# TSAL_PL.net
KiCad netlist of a schematic drawn in Altium Designer
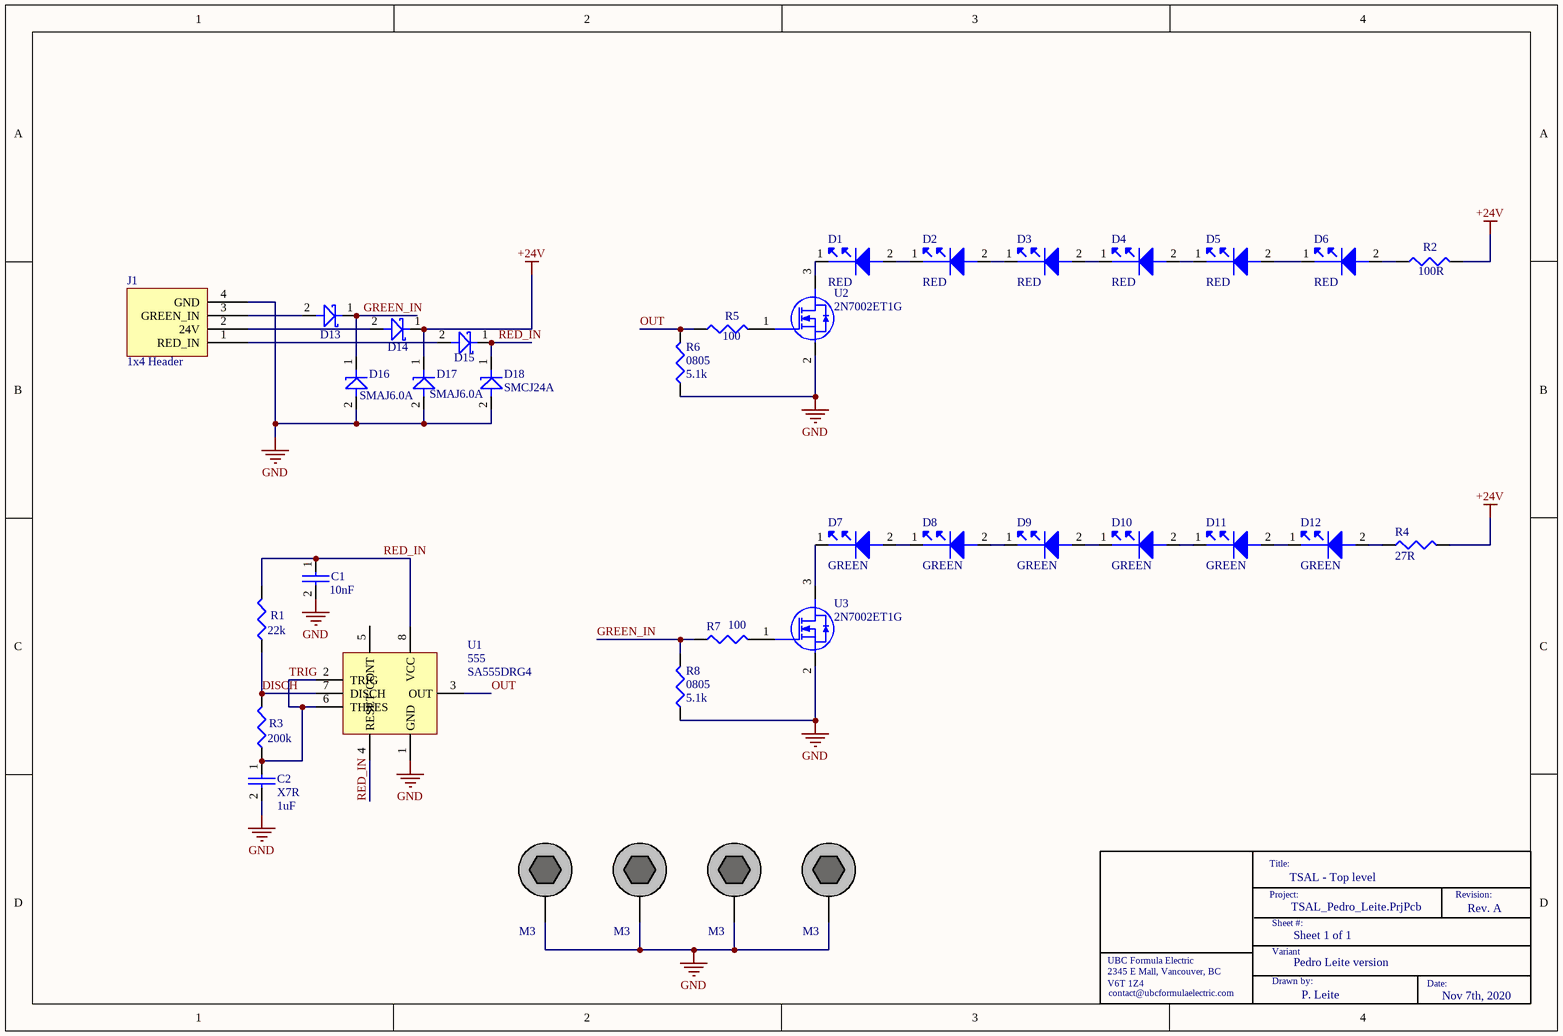
[diagram p0: TSAL_PL.SchDoc]

(export (version "E")
  (design (tool "Eeschema 10.0.6"))
  (components
    (comp (ref "*") (value "Title Box") (libsource (lib "TSAL_PL") (part "Title Box")))
    (comp (ref "2")
      (value "M3")
      (footprint "M3 Mounting Hole")
      (libsource (lib "UBC Formula Electric") (part "M3 Mounting Hole"))
    )
    (comp (ref "3")
      (value "M3")
      (footprint "M3 Mounting Hole")
      (libsource (lib "UBC Formula Electric") (part "M3 Mounting Hole"))
    )
    (comp (ref "4")
      (value "M3")
      (footprint "M3 Mounting Hole")
      (libsource (lib "UBC Formula Electric") (part "M3 Mounting Hole"))
    )
    (comp (ref "C1")
      (value "0603")
      (footprint "0603 CAPACITOR (TDK C-SERIES)")
      (description "Cap Ceramic 0.01uF 50VDC X7R 10% SMD 0603 Paper T/R")
      (fields
        (field (name "MANUFACTURER") "Samsung")
        (field (name "MANUFACTURER PART NUMBER") "CL10B103KB8NNNC")
        (field (name "CAPACITANCE") "10nF")
      )
      (libsource (lib "TSAL_PL") (part "CL10B103KB8NNNC"))
    )
    (comp (ref "C2")
      (value "X7R")
      (footprint "RESC0805X60N")
      (fields
        (field (name "MANUFACTURER") "Yageo")
        (field (name "MANUFACTURER PART NUMBER") "CC0805KKX7R6BB105")
        (field (name "TOLERANCE") "10%")
        (field (name "CAPACITANCE") "1uF")
      )
      (libsource (lib "TSAL_PL") (part "CC0805KKX7R6BB105"))
    )
    (comp (ref "D1")
      (value "RED")
      (footprint "RED LED")
      (description "LED 0.33W RED WTR CLR 3.5MM")
      (fields (field (name "MANUFACTURER") "TT Optek") (field (name "MANUFACTURER PART NUMBER") "OVS5MRBCR4"))
      (libsource (lib "TSAL_PL") (part "OVS5MRBCR4"))
    )
    (comp (ref "D2")
      (value "RED")
      (footprint "RED LED")
      (description "LED 0.33W RED WTR CLR 3.5MM")
      (fields (field (name "MANUFACTURER") "TT Optek") (field (name "MANUFACTURER PART NUMBER") "OVS5MRBCR4"))
      (libsource (lib "TSAL_PL") (part "OVS5MRBCR4"))
    )
    (comp (ref "D3")
      (value "RED")
      (footprint "RED LED")
      (description "LED 0.33W RED WTR CLR 3.5MM")
      (fields (field (name "MANUFACTURER") "TT Optek") (field (name "MANUFACTURER PART NUMBER") "OVS5MRBCR4"))
      (libsource (lib "TSAL_PL") (part "OVS5MRBCR4"))
    )
    (comp (ref "D4")
      (value "RED")
      (footprint "RED LED")
      (description "LED 0.33W RED WTR CLR 3.5MM")
      (fields (field (name "MANUFACTURER") "TT Optek") (field (name "MANUFACTURER PART NUMBER") "OVS5MRBCR4"))
      (libsource (lib "TSAL_PL") (part "OVS5MRBCR4"))
    )
    (comp (ref "D5")
      (value "RED")
      (footprint "RED LED")
      (description "LED 0.33W RED WTR CLR 3.5MM")
      (fields (field (name "MANUFACTURER") "TT Optek") (field (name "MANUFACTURER PART NUMBER") "OVS5MRBCR4"))
      (libsource (lib "TSAL_PL") (part "OVS5MRBCR4"))
    )
    (comp (ref "D6")
      (value "RED")
      (footprint "RED LED")
      (description "LED 0.33W RED WTR CLR 3.5MM")
      (fields (field (name "MANUFACTURER") "TT Optek") (field (name "MANUFACTURER PART NUMBER") "OVS5MRBCR4"))
      (libsource (lib "TSAL_PL") (part "OVS5MRBCR4"))
    )
    (comp (ref "D7")
      (value "GREEN")
      (footprint "GREEN LED")
      (description "Led 3.5X2.8 0.5W SMD Green")
      (fields (field (name "MANUFACTURER") "SunLED") (field (name "MANUFACTURER PART NUMBER") "XZDG25X109FS"))
      (libsource (lib "TSAL_PL") (part "XZDG25X109FS"))
    )
    (comp (ref "D8")
      (value "GREEN")
      (footprint "GREEN LED")
      (description "Led 3.5X2.8 0.5W SMD Green")
      (fields (field (name "MANUFACTURER") "SunLED") (field (name "MANUFACTURER PART NUMBER") "XZDG25X109FS"))
      (libsource (lib "TSAL_PL") (part "XZDG25X109FS"))
    )
    (comp (ref "D9")
      (value "GREEN")
      (footprint "GREEN LED")
      (description "Led 3.5X2.8 0.5W SMD Green")
      (fields (field (name "MANUFACTURER") "SunLED") (field (name "MANUFACTURER PART NUMBER") "XZDG25X109FS"))
      (libsource (lib "TSAL_PL") (part "XZDG25X109FS"))
    )
    (comp (ref "D10")
      (value "GREEN")
      (footprint "GREEN LED")
      (description "Led 3.5X2.8 0.5W SMD Green")
      (fields (field (name "MANUFACTURER") "SunLED") (field (name "MANUFACTURER PART NUMBER") "XZDG25X109FS"))
      (libsource (lib "TSAL_PL") (part "XZDG25X109FS"))
    )
    (comp (ref "D11")
      (value "GREEN")
      (footprint "GREEN LED")
      (description "Led 3.5X2.8 0.5W SMD Green")
      (fields (field (name "MANUFACTURER") "SunLED") (field (name "MANUFACTURER PART NUMBER") "XZDG25X109FS"))
      (libsource (lib "TSAL_PL") (part "XZDG25X109FS"))
    )
    (comp (ref "D12")
      (value "GREEN")
      (footprint "GREEN LED")
      (description "Led 3.5X2.8 0.5W SMD Green")
      (fields (field (name "MANUFACTURER") "SunLED") (field (name "MANUFACTURER PART NUMBER") "XZDG25X109FS"))
      (libsource (lib "TSAL_PL") (part "XZDG25X109FS"))
    )
    (comp (ref "D13")
      (value "NRVTS260ESFT1G")
      (footprint "ON NRVTS260ESFT1G")
      (description "ON SEMICONDUCTOR - NRVTS260ESFT1G - Schottky Rectifier, 60 V, 2 A, Single, SOD-123, 2 Pins, 650 mV")
      (fields (field (name "MANUFACTURER") "ON Semiconductor"))
      (libsource (lib "TSAL_PL") (part "NRVTS260ESFT1G"))
    )
    (comp (ref "D14")
      (value "NRVTS260ESFT1G")
      (footprint "ON NRVTS260ESFT1G")
      (description "ON SEMICONDUCTOR - NRVTS260ESFT1G - Schottky Rectifier, 60 V, 2 A, Single, SOD-123, 2 Pins, 650 mV")
      (fields (field (name "MANUFACTURER") "ON Semiconductor"))
      (libsource (lib "TSAL_PL") (part "NRVTS260ESFT1G"))
    )
    (comp (ref "D15")
      (value "NRVTS260ESFT1G")
      (footprint "ON NRVTS260ESFT1G")
      (description "ON SEMICONDUCTOR - NRVTS260ESFT1G - Schottky Rectifier, 60 V, 2 A, Single, SOD-123, 2 Pins, 650 mV")
      (fields (field (name "MANUFACTURER") "ON Semiconductor"))
      (libsource (lib "TSAL_PL") (part "NRVTS260ESFT1G"))
    )
    (comp (ref "D16")
      (value "SMAJ6.0A")
      (footprint "LITTELFUSE SMAJ6.0A")
      (description "In a Pack of 25, Littelfuse SMAJ6.0A, Uni-Directional TVS Diode, 400W, 2-Pin DO-214AC")
      (fields (field (name "MANUFACTURER") "Littelfuse") (field (name "VOLTAGE") "60V"))
      (libsource (lib "TSAL_PL") (part "SMAJ6.0A"))
    )
    (comp (ref "D17")
      (value "SMAJ6.0A")
      (footprint "LITTELFUSE SMAJ6.0A")
      (description "In a Pack of 25, Littelfuse SMAJ6.0A, Uni-Directional TVS Diode, 400W, 2-Pin DO-214AC")
      (fields (field (name "MANUFACTURER") "Littelfuse") (field (name "VOLTAGE") "60V"))
      (libsource (lib "TSAL_PL") (part "SMAJ6.0A"))
    )
    (comp (ref "D18")
      (value "SMCJ24A")
      (footprint "LITTELFUSE SMCJ24A")
      (fields (field (name "MANUFACTURER") "Littelfuse"))
      (libsource (lib "TSAL_PL") (part "SMCJ24A"))
    )
    (comp (ref "J1")
      (value "1x4 Header")
      (footprint "HDR1x4")
      (description "Conn Wire to Board HDR 4 POS 2.54mm Solder ST Thru-Hole Bag")
      (fields (field (name "MANUFACTURER") "Molex") (field (name "MANUFACTURER PART NUMBER") "22-27-2041"))
      (libsource (lib "TSAL_PL") (part "22-27-2041"))
    )
    (comp (ref "M1")
      (value "M3")
      (footprint "M3 Mounting Hole")
      (libsource (lib "UBC Formula Electric") (part "M3 Mounting Hole"))
    )
    (comp (ref "R1")
      (value "0603")
      (footprint "0603 RESISTOR (YAGEO)")
      (description "Res Thick Film 0603 22K Ohm 1% 1/10W ±100ppm/°C Molded SMD Paper T/R")
      (fields
        (field (name "MANUFACTURER") "Vishay Semiconductors")
        (field (name "MANUFACTURER PART NUMBER") "CRCW060322K0FKEAC")
        (field (name "RESISTANCE") "22k")
      )
      (libsource (lib "TSAL_PL") (part "CRCW060322K0FKEAC"))
    )
    (comp (ref "R2")
      (value "2010")
      (footprint "2010 RESISTOR (YAGEO)")
      (description "TE CONNECTIVITY - CRGP2010F100R - RES, 100R, 1%, 1.25W, 2010, THICK FILM")
      (fields
        (field (name "MANUFACTURER") "TE Connectivity")
        (field (name "MANUFACTURER PART NUMBER") "CRGP2010F100R")
        (field (name "RESISTENCE") "100R")
      )
      (libsource (lib "TSAL_PL") (part "2010"))
    )
    (comp (ref "R3")
      (value "0603")
      (footprint "0603 RESISTOR (YAGEO)")
      (description "Res Thick Film 0603 200K Ohm 1% 1/10W ±100ppm/°C Molded SMD Paper T/R")
      (fields
        (field (name "MANUFACTURER") "Vishay")
        (field (name "MANUFACTURER PART NUMBER") "CRCW0603200KFKEAC")
        (field (name "RESISTANCE") "200k")
      )
      (libsource (lib "TSAL_PL") (part "CRCW0603200KFKEAC"))
    )
    (comp (ref "R4")
      (value "RL1220S-270-F")
      (footprint "0805 RESISTOR (YAGEO)")
      (description "RES SMD 27 OHM 1% 1/3W 0805")
      (fields (field (name "MANUFACTURER") "Susumu") (field (name "RESISTANCE") "27R"))
      (libsource (lib "TSAL_PL") (part "RL1220S-270-F"))
    )
    (comp (ref "R5")
      (value "0805")
      (footprint "0805 RESISTOR (YAGEO)")
      (description "RES SMD 100 OHM 0.5% 1/8W 0805")
      (fields
        (field (name "MANUFACTURER") "Yageo")
        (field (name "MANUFACTURER PART NUMBER") "RT0805DRD07100RL")
        (field (name "RESISTANCE") "100")
      )
      (libsource (lib "TSAL_PL") (part "RT0805DRD07100RL"))
    )
    (comp (ref "R6")
      (value "0805")
      (footprint "0805 RESISTOR (YAGEO)")
      (description "Res Thick Film 0805 5.1K Ohm 5% 0.125W(1/8W) ±100ppm/C Epoxy Pad SMD T/R")
      (fields
        (field (name "MANUFACTURER") "Yageo")
        (field (name "MANUFACTURER PART NUMBER") "RC0805JR-075K1L")
        (field (name "RESISTANCE") "5.1k")
      )
      (libsource (lib "TSAL_PL") (part "RC0805JR-075K1L"))
    )
    (comp (ref "R7")
      (value "0805")
      (footprint "0805 RESISTOR (YAGEO)")
      (description "RES SMD 100 OHM 0.5% 1/8W 0805")
      (fields
        (field (name "MANUFACTURER") "Yageo")
        (field (name "MANUFACTURER PART NUMBER") "RT0805DRD07100RL")
        (field (name "RESISTANCE") "100")
      )
      (libsource (lib "TSAL_PL") (part "RT0805DRD07100RL"))
    )
    (comp (ref "R8")
      (value "0805")
      (footprint "0805 RESISTOR (YAGEO)")
      (description "Res Thick Film 0805 5.1K Ohm 5% 0.125W(1/8W) ±100ppm/C Epoxy Pad SMD T/R")
      (fields
        (field (name "MANUFACTURER") "Yageo")
        (field (name "MANUFACTURER PART NUMBER") "RC0805JR-075K1L")
        (field (name "RESISTANCE") "5.1k")
      )
      (libsource (lib "TSAL_PL") (part "RC0805JR-075K1L"))
    )
    (comp (ref "U1")
      (value "555")
      (footprint "SOIC-8")
      (description "IC OSC SGL TIMER 100KHZ 8-SOIC")
      (fields
        (field (name "MANUFACTURER") "Texas Instruments")
        (field (name "MANUFACTURER PART NUMBER") "SA555DRG4")
      )
      (libsource (lib "TSAL_PL") (part "SA555DRG4"))
    )
    (comp (ref "U2")
      (value "2N7002ET1G")
      (footprint "2N7002ET1G")
      (description "Trans MOSFET N-CH 60V 0.26A 3-Pin SOT-23 T/R")
      (fields (field (name "MANUFACTURER") "ON Semiconductor"))
      (libsource (lib "TSAL_PL") (part "2N7002ET1G"))
    )
    (comp (ref "U3")
      (value "2N7002ET1G")
      (footprint "2N7002ET1G")
      (description "Trans MOSFET N-CH 60V 0.26A 3-Pin SOT-23 T/R")
      (fields (field (name "MANUFACTURER") "ON Semiconductor"))
      (libsource (lib "TSAL_PL") (part "2N7002ET1G"))
    )
  )
  (nets
    (net (code "1") (name "+24V") (class "Default")
      (node (ref "D14") (pin "1") (pinfunction "1_1") (pintype "passive"))
      (node (ref "D17") (pin "1") (pinfunction "1_1") (pintype "passive"))
      (node (ref "R2") (pin "2") (pinfunction "2_2") (pintype "passive"))
      (node (ref "R4") (pin "2") (pinfunction "2_2") (pintype "passive"))
    )
    (net (code "2") (name "/DISCH") (class "Default")
      (node (ref "R1") (pin "1") (pinfunction "1_1") (pintype "passive"))
      (node (ref "R3") (pin "2") (pinfunction "2_2") (pintype "passive"))
      (node (ref "U1") (pin "7") (pinfunction "DISCH_7") (pintype "passive"))
    )
    (net (code "3") (name "/GREEN_IN") (class "Default")
      (node (ref "D13") (pin "1") (pinfunction "1_1") (pintype "passive"))
      (node (ref "D16") (pin "1") (pinfunction "1_1") (pintype "passive"))
      (node (ref "R7") (pin "1") (pinfunction "1_1") (pintype "passive"))
      (node (ref "R8") (pin "2") (pinfunction "2_2") (pintype "passive"))
    )
    (net (code "4") (name "/OUT") (class "Default")
      (node (ref "R5") (pin "1") (pinfunction "1_1") (pintype "passive"))
      (node (ref "R6") (pin "2") (pinfunction "2_2") (pintype "passive"))
      (node (ref "U1") (pin "3") (pinfunction "OUT_3") (pintype "passive"))
    )
    (net (code "5") (name "/RED_IN") (class "Default")
      (node (ref "C1") (pin "1") (pinfunction "1_1") (pintype "passive"))
      (node (ref "D15") (pin "1") (pinfunction "1_1") (pintype "passive"))
      (node (ref "D18") (pin "1") (pinfunction "1_1") (pintype "passive"))
      (node (ref "R1") (pin "2") (pinfunction "2_2") (pintype "passive"))
      (node (ref "U1") (pin "4") (pinfunction "RESET_4") (pintype "passive"))
      (node (ref "U1") (pin "8") (pinfunction "VCC_8") (pintype "passive"))
    )
    (net (code "6") (name "/TRIG") (class "Default")
      (node (ref "C2") (pin "1") (pinfunction "1_1") (pintype "passive"))
      (node (ref "R3") (pin "1") (pinfunction "1_1") (pintype "passive"))
      (node (ref "U1") (pin "2") (pinfunction "TRIG_2") (pintype "passive"))
      (node (ref "U1") (pin "6") (pinfunction "THRES_6") (pintype "passive"))
    )
    (net (code "7") (name "GND") (class "Default")
      (node (ref "2") (pin "1") (pinfunction "1_1") (pintype "passive"))
      (node (ref "3") (pin "1") (pinfunction "1_1") (pintype "passive"))
      (node (ref "4") (pin "1") (pinfunction "1_1") (pintype "passive"))
      (node (ref "C1") (pin "2") (pinfunction "2_2") (pintype "passive"))
      (node (ref "C2") (pin "2") (pinfunction "2_2") (pintype "passive"))
      (node (ref "D16") (pin "2") (pinfunction "2_2") (pintype "passive"))
      (node (ref "D17") (pin "2") (pinfunction "2_2") (pintype "passive"))
      (node (ref "D18") (pin "2") (pinfunction "2_2") (pintype "passive"))
      (node (ref "J1") (pin "4") (pinfunction "GND_4") (pintype "passive"))
      (node (ref "M1") (pin "1") (pinfunction "1_1") (pintype "passive"))
      (node (ref "R6") (pin "1") (pinfunction "1_1") (pintype "passive"))
      (node (ref "R8") (pin "1") (pinfunction "1_1") (pintype "passive"))
      (node (ref "U1") (pin "1") (pinfunction "GND_1") (pintype "passive"))
      (node (ref "U2") (pin "2") (pinfunction "S_2") (pintype "passive"))
      (node (ref "U3") (pin "2") (pinfunction "S_2") (pintype "passive"))
    )
    (net (code "8") (name "Net-(D1-Pad2)") (class "Default")
      (node (ref "D1") (pin "2") (pinfunction "2_2") (pintype "passive"))
      (node (ref "D2") (pin "1") (pinfunction "1_1") (pintype "passive"))
    )
    (net (code "9") (name "Net-(D2-Pad2)") (class "Default")
      (node (ref "D2") (pin "2") (pinfunction "2_2") (pintype "passive"))
      (node (ref "D3") (pin "1") (pinfunction "1_1") (pintype "passive"))
    )
    (net (code "10") (name "Net-(D3-Pad2)") (class "Default")
      (node (ref "D3") (pin "2") (pinfunction "2_2") (pintype "passive"))
      (node (ref "D4") (pin "1") (pinfunction "1_1") (pintype "passive"))
    )
    (net (code "11") (name "Net-(D4-Pad2)") (class "Default")
      (node (ref "D4") (pin "2") (pinfunction "2_2") (pintype "passive"))
      (node (ref "D5") (pin "1") (pinfunction "1_1") (pintype "passive"))
    )
    (net (code "12") (name "Net-(D5-Pad2)") (class "Default")
      (node (ref "D5") (pin "2") (pinfunction "2_2") (pintype "passive"))
      (node (ref "D6") (pin "1") (pinfunction "1_1") (pintype "passive"))
    )
    (net (code "13") (name "Net-(D6-Pad2)") (class "Default")
      (node (ref "D6") (pin "2") (pinfunction "2_2") (pintype "passive"))
      (node (ref "R2") (pin "1") (pinfunction "1_1") (pintype "passive"))
    )
    (net (code "14") (name "Net-(D7-Pad2)") (class "Default")
      (node (ref "D7") (pin "2") (pinfunction "2_2") (pintype "passive"))
      (node (ref "D8") (pin "1") (pinfunction "1_1") (pintype "passive"))
    )
    (net (code "15") (name "Net-(D8-Pad2)") (class "Default")
      (node (ref "D8") (pin "2") (pinfunction "2_2") (pintype "passive"))
      (node (ref "D9") (pin "1") (pinfunction "1_1") (pintype "passive"))
    )
    (net (code "16") (name "Net-(D10-Pad1)") (class "Default")
      (node (ref "D10") (pin "1") (pinfunction "1_1") (pintype "passive"))
      (node (ref "D9") (pin "2") (pinfunction "2_2") (pintype "passive"))
    )
    (net (code "17") (name "Net-(D10-Pad2)") (class "Default")
      (node (ref "D10") (pin "2") (pinfunction "2_2") (pintype "passive"))
      (node (ref "D11") (pin "1") (pinfunction "1_1") (pintype "passive"))
    )
    (net (code "18") (name "Net-(D11-Pad2)") (class "Default")
      (node (ref "D11") (pin "2") (pinfunction "2_2") (pintype "passive"))
      (node (ref "D12") (pin "1") (pinfunction "1_1") (pintype "passive"))
    )
    (net (code "19") (name "Net-(D12-Pad2)") (class "Default")
      (node (ref "D12") (pin "2") (pinfunction "2_2") (pintype "passive"))
      (node (ref "R4") (pin "1") (pinfunction "1_1") (pintype "passive"))
    )
    (net (code "20") (name "Net-(J1-24V)") (class "Default")
      (node (ref "D14") (pin "2") (pinfunction "2_2") (pintype "passive"))
      (node (ref "J1") (pin "2") (pinfunction "24V_2") (pintype "passive"))
    )
    (net (code "21") (name "Net-(J1-GREEN_IN)") (class "Default")
      (node (ref "D13") (pin "2") (pinfunction "2_2") (pintype "passive"))
      (node (ref "J1") (pin "3") (pinfunction "GREEN_IN_3") (pintype "passive"))
    )
    (net (code "22") (name "Net-(J1-RED_IN)") (class "Default")
      (node (ref "D15") (pin "2") (pinfunction "2_2") (pintype "passive"))
      (node (ref "J1") (pin "1") (pinfunction "RED_IN_1") (pintype "passive"))
    )
    (net (code "23") (name "Net-(U2-D)") (class "Default")
      (node (ref "D1") (pin "1") (pinfunction "1_1") (pintype "passive"))
      (node (ref "U2") (pin "3") (pinfunction "D_3") (pintype "passive"))
    )
    (net (code "24") (name "Net-(U2-G)") (class "Default")
      (node (ref "R5") (pin "2") (pinfunction "2_2") (pintype "passive"))
      (node (ref "U2") (pin "1") (pinfunction "G_1") (pintype "passive"))
    )
    (net (code "25") (name "Net-(U3-D)") (class "Default")
      (node (ref "D7") (pin "1") (pinfunction "1_1") (pintype "passive"))
      (node (ref "U3") (pin "3") (pinfunction "D_3") (pintype "passive"))
    )
    (net (code "26") (name "Net-(U3-G)") (class "Default")
      (node (ref "R7") (pin "2") (pinfunction "2_2") (pintype "passive"))
      (node (ref "U3") (pin "1") (pinfunction "G_1") (pintype "passive"))
    )
    (net (code "27") (name "unconnected-(U1-CONT-Pad5)") (class "Default")
      (node (ref "U1") (pin "5") (pinfunction "CONT_5") (pintype "passive"))
    )
  )
)
